# Ganggu.net
KiCad netlist of a schematic drawn in EAGLE
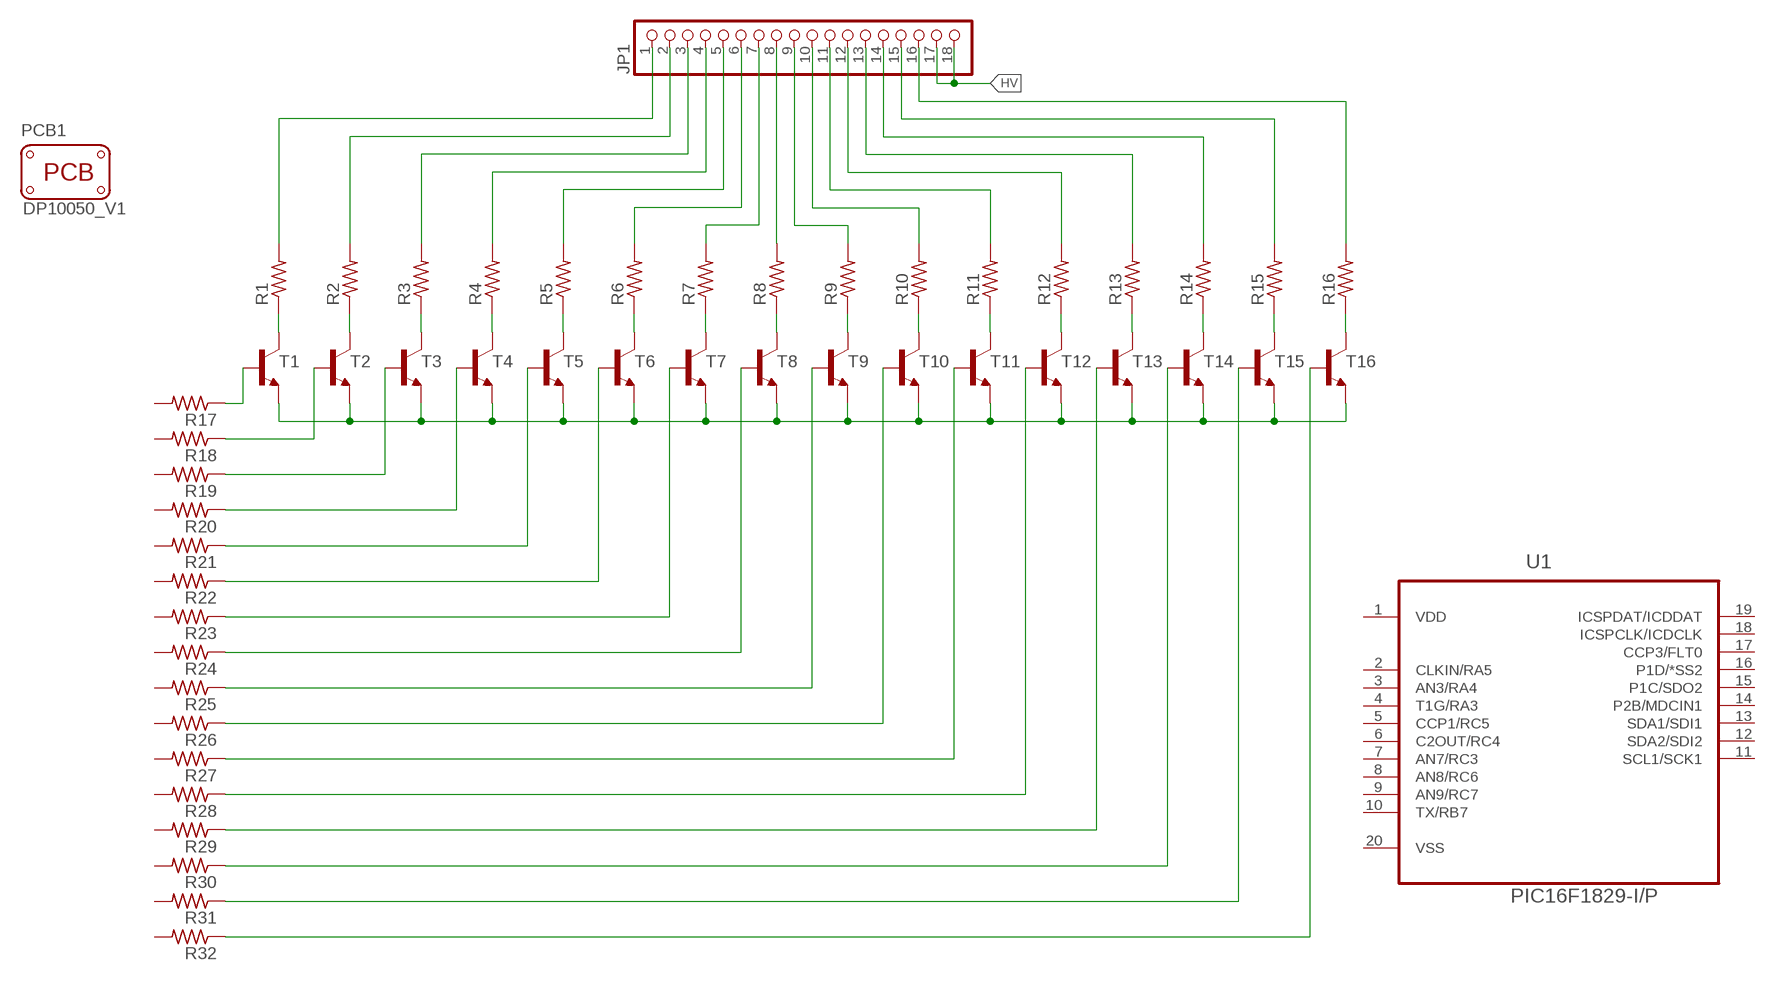
[diagram p0: schematic, sheet 1]

(export (version "E")
  (design (tool "Eeschema 10.0.6"))
  (components
    (comp (ref "JP1")
      (value "PINHD-1X18")
      (footprint "eagle-import:1X18")
      (libsource (lib "eagle-import") (part "PINHD-1X18"))
    )
    (comp (ref "PCB1")
      (value "PCB_DP_RECTANGLE-50X100")
      (footprint "eagle-import:DP10050_V1")
      (libsource (lib "eagle-import") (part "PCB_DP_RECTANGLE-50X100"))
    )
    (comp (ref "R1")
      (value "R-US_0207/9")
      (footprint "eagle-import:0207_9")
      (libsource (lib "eagle-import") (part "R-US_0207/9"))
    )
    (comp (ref "R2")
      (value "R-US_0207/9")
      (footprint "eagle-import:0207_9")
      (libsource (lib "eagle-import") (part "R-US_0207/9"))
    )
    (comp (ref "R3")
      (value "R-US_0207/9")
      (footprint "eagle-import:0207_9")
      (libsource (lib "eagle-import") (part "R-US_0207/9"))
    )
    (comp (ref "R4")
      (value "R-US_0207/9")
      (footprint "eagle-import:0207_9")
      (libsource (lib "eagle-import") (part "R-US_0207/9"))
    )
    (comp (ref "R5")
      (value "R-US_0207/9")
      (footprint "eagle-import:0207_9")
      (libsource (lib "eagle-import") (part "R-US_0207/9"))
    )
    (comp (ref "R6")
      (value "R-US_0207/9")
      (footprint "eagle-import:0207_9")
      (libsource (lib "eagle-import") (part "R-US_0207/9"))
    )
    (comp (ref "R7")
      (value "R-US_0207/9")
      (footprint "eagle-import:0207_9")
      (libsource (lib "eagle-import") (part "R-US_0207/9"))
    )
    (comp (ref "R8")
      (value "R-US_0207/9")
      (footprint "eagle-import:0207_9")
      (libsource (lib "eagle-import") (part "R-US_0207/9"))
    )
    (comp (ref "R9")
      (value "R-US_0207/9")
      (footprint "eagle-import:0207_9")
      (libsource (lib "eagle-import") (part "R-US_0207/9"))
    )
    (comp (ref "R10")
      (value "R-US_0207/9")
      (footprint "eagle-import:0207_9")
      (libsource (lib "eagle-import") (part "R-US_0207/9"))
    )
    (comp (ref "R11")
      (value "R-US_0207/9")
      (footprint "eagle-import:0207_9")
      (libsource (lib "eagle-import") (part "R-US_0207/9"))
    )
    (comp (ref "R12")
      (value "R-US_0207/9")
      (footprint "eagle-import:0207_9")
      (libsource (lib "eagle-import") (part "R-US_0207/9"))
    )
    (comp (ref "R13")
      (value "R-US_0207/9")
      (footprint "eagle-import:0207_9")
      (libsource (lib "eagle-import") (part "R-US_0207/9"))
    )
    (comp (ref "R14")
      (value "R-US_0207/9")
      (footprint "eagle-import:0207_9")
      (libsource (lib "eagle-import") (part "R-US_0207/9"))
    )
    (comp (ref "R15")
      (value "R-US_0207/9")
      (footprint "eagle-import:0207_9")
      (libsource (lib "eagle-import") (part "R-US_0207/9"))
    )
    (comp (ref "R16")
      (value "R-US_0207/9")
      (footprint "eagle-import:0207_9")
      (libsource (lib "eagle-import") (part "R-US_0207/9"))
    )
    (comp (ref "R17")
      (value "R-US_0207/9")
      (footprint "eagle-import:0207_9")
      (libsource (lib "eagle-import") (part "R-US_0207/9"))
    )
    (comp (ref "R18")
      (value "R-US_0207/9")
      (footprint "eagle-import:0207_9")
      (libsource (lib "eagle-import") (part "R-US_0207/9"))
    )
    (comp (ref "R19")
      (value "R-US_0207/9")
      (footprint "eagle-import:0207_9")
      (libsource (lib "eagle-import") (part "R-US_0207/9"))
    )
    (comp (ref "R20")
      (value "R-US_0207/9")
      (footprint "eagle-import:0207_9")
      (libsource (lib "eagle-import") (part "R-US_0207/9"))
    )
    (comp (ref "R21")
      (value "R-US_0207/9")
      (footprint "eagle-import:0207_9")
      (libsource (lib "eagle-import") (part "R-US_0207/9"))
    )
    (comp (ref "R22")
      (value "R-US_0207/9")
      (footprint "eagle-import:0207_9")
      (libsource (lib "eagle-import") (part "R-US_0207/9"))
    )
    (comp (ref "R23")
      (value "R-US_0207/9")
      (footprint "eagle-import:0207_9")
      (libsource (lib "eagle-import") (part "R-US_0207/9"))
    )
    (comp (ref "R24")
      (value "R-US_0207/9")
      (footprint "eagle-import:0207_9")
      (libsource (lib "eagle-import") (part "R-US_0207/9"))
    )
    (comp (ref "R25")
      (value "R-US_0207/9")
      (footprint "eagle-import:0207_9")
      (libsource (lib "eagle-import") (part "R-US_0207/9"))
    )
    (comp (ref "R26")
      (value "R-US_0207/9")
      (footprint "eagle-import:0207_9")
      (libsource (lib "eagle-import") (part "R-US_0207/9"))
    )
    (comp (ref "R27")
      (value "R-US_0207/9")
      (footprint "eagle-import:0207_9")
      (libsource (lib "eagle-import") (part "R-US_0207/9"))
    )
    (comp (ref "R28")
      (value "R-US_0207/9")
      (footprint "eagle-import:0207_9")
      (libsource (lib "eagle-import") (part "R-US_0207/9"))
    )
    (comp (ref "R29")
      (value "R-US_0207/9")
      (footprint "eagle-import:0207_9")
      (libsource (lib "eagle-import") (part "R-US_0207/9"))
    )
    (comp (ref "R30")
      (value "R-US_0207/9")
      (footprint "eagle-import:0207_9")
      (libsource (lib "eagle-import") (part "R-US_0207/9"))
    )
    (comp (ref "R31")
      (value "R-US_0207/9")
      (footprint "eagle-import:0207_9")
      (libsource (lib "eagle-import") (part "R-US_0207/9"))
    )
    (comp (ref "R32")
      (value "R-US_0207/9")
      (footprint "eagle-import:0207_9")
      (libsource (lib "eagle-import") (part "R-US_0207/9"))
    )
    (comp (ref "T1")
      (value "2N2222")
      (footprint "eagle-import:TO92-EBC-OVAL")
      (libsource (lib "eagle-import") (part "2N2222"))
    )
    (comp (ref "T2")
      (value "2N2222")
      (footprint "eagle-import:TO92-EBC-OVAL")
      (libsource (lib "eagle-import") (part "2N2222"))
    )
    (comp (ref "T3")
      (value "2N2222")
      (footprint "eagle-import:TO92-EBC-OVAL")
      (libsource (lib "eagle-import") (part "2N2222"))
    )
    (comp (ref "T4")
      (value "2N2222")
      (footprint "eagle-import:TO92-EBC-OVAL")
      (libsource (lib "eagle-import") (part "2N2222"))
    )
    (comp (ref "T5")
      (value "2N2222")
      (footprint "eagle-import:TO92-EBC-OVAL")
      (libsource (lib "eagle-import") (part "2N2222"))
    )
    (comp (ref "T6")
      (value "2N2222")
      (footprint "eagle-import:TO92-EBC-OVAL")
      (libsource (lib "eagle-import") (part "2N2222"))
    )
    (comp (ref "T7")
      (value "2N2222")
      (footprint "eagle-import:TO92-EBC-OVAL")
      (libsource (lib "eagle-import") (part "2N2222"))
    )
    (comp (ref "T8")
      (value "2N2222")
      (footprint "eagle-import:TO92-EBC-OVAL")
      (libsource (lib "eagle-import") (part "2N2222"))
    )
    (comp (ref "T9")
      (value "2N2222")
      (footprint "eagle-import:TO92-EBC-OVAL")
      (libsource (lib "eagle-import") (part "2N2222"))
    )
    (comp (ref "T10")
      (value "2N2222")
      (footprint "eagle-import:TO92-EBC-OVAL")
      (libsource (lib "eagle-import") (part "2N2222"))
    )
    (comp (ref "T11")
      (value "2N2222")
      (footprint "eagle-import:TO92-EBC-OVAL")
      (libsource (lib "eagle-import") (part "2N2222"))
    )
    (comp (ref "T12")
      (value "2N2222")
      (footprint "eagle-import:TO92-EBC-OVAL")
      (libsource (lib "eagle-import") (part "2N2222"))
    )
    (comp (ref "T13")
      (value "2N2222")
      (footprint "eagle-import:TO92-EBC-OVAL")
      (libsource (lib "eagle-import") (part "2N2222"))
    )
    (comp (ref "T14")
      (value "2N2222")
      (footprint "eagle-import:TO92-EBC-OVAL")
      (libsource (lib "eagle-import") (part "2N2222"))
    )
    (comp (ref "T15")
      (value "2N2222")
      (footprint "eagle-import:TO92-EBC-OVAL")
      (libsource (lib "eagle-import") (part "2N2222"))
    )
    (comp (ref "T16")
      (value "2N2222")
      (footprint "eagle-import:TO92-EBC-OVAL")
      (libsource (lib "eagle-import") (part "2N2222"))
    )
    (comp (ref "U1")
      (value "PIC16F1829-I/P")
      (footprint "eagle-import:DIP254P762X508-20P")
      (libsource (lib "eagle-import") (part "PIC16F1829-I/P"))
    )
  )
  (nets
    (net (code "1") (name "/VDD") (class "Default")
      (node (ref "U1") (pin "1") (pinfunction "VDD_1") (pintype "power_in"))
    )
    (net (code "2") (name "/VSS") (class "Default")
      (node (ref "U1") (pin "20") (pinfunction "VSS_20") (pintype "power_in"))
    )
    (net (code "3") (name "HV") (class "Default")
      (node (ref "JP1") (pin "17") (pinfunction "17_17") (pintype "passive"))
      (node (ref "JP1") (pin "18") (pinfunction "18_18") (pintype "passive"))
    )
    (net (code "4") (name "Net-(JP1-Pad1)") (class "Default")
      (node (ref "JP1") (pin "1") (pinfunction "1_1") (pintype "passive"))
      (node (ref "R1") (pin "2") (pinfunction "2_2") (pintype "passive"))
    )
    (net (code "5") (name "Net-(JP1-Pad2)") (class "Default")
      (node (ref "JP1") (pin "2") (pinfunction "2_2") (pintype "passive"))
      (node (ref "R2") (pin "2") (pinfunction "2_2") (pintype "passive"))
    )
    (net (code "6") (name "Net-(JP1-Pad3)") (class "Default")
      (node (ref "JP1") (pin "3") (pinfunction "3_3") (pintype "passive"))
      (node (ref "R3") (pin "2") (pinfunction "2_2") (pintype "passive"))
    )
    (net (code "7") (name "Net-(JP1-Pad4)") (class "Default")
      (node (ref "JP1") (pin "4") (pinfunction "4_4") (pintype "passive"))
      (node (ref "R4") (pin "2") (pinfunction "2_2") (pintype "passive"))
    )
    (net (code "8") (name "Net-(JP1-Pad5)") (class "Default")
      (node (ref "JP1") (pin "5") (pinfunction "5_5") (pintype "passive"))
      (node (ref "R5") (pin "2") (pinfunction "2_2") (pintype "passive"))
    )
    (net (code "9") (name "Net-(JP1-Pad6)") (class "Default")
      (node (ref "JP1") (pin "6") (pinfunction "6_6") (pintype "passive"))
      (node (ref "R6") (pin "2") (pinfunction "2_2") (pintype "passive"))
    )
    (net (code "10") (name "Net-(JP1-Pad7)") (class "Default")
      (node (ref "JP1") (pin "7") (pinfunction "7_7") (pintype "passive"))
      (node (ref "R7") (pin "2") (pinfunction "2_2") (pintype "passive"))
    )
    (net (code "11") (name "Net-(JP1-Pad8)") (class "Default")
      (node (ref "JP1") (pin "8") (pinfunction "8_8") (pintype "passive"))
      (node (ref "R8") (pin "2") (pinfunction "2_2") (pintype "passive"))
    )
    (net (code "12") (name "Net-(JP1-Pad9)") (class "Default")
      (node (ref "JP1") (pin "9") (pinfunction "9_9") (pintype "passive"))
      (node (ref "R9") (pin "2") (pinfunction "2_2") (pintype "passive"))
    )
    (net (code "13") (name "Net-(JP1-Pad10)") (class "Default")
      (node (ref "JP1") (pin "10") (pinfunction "10_10") (pintype "passive"))
      (node (ref "R10") (pin "2") (pinfunction "2_2") (pintype "passive"))
    )
    (net (code "14") (name "Net-(JP1-Pad11)") (class "Default")
      (node (ref "JP1") (pin "11") (pinfunction "11_11") (pintype "passive"))
      (node (ref "R11") (pin "2") (pinfunction "2_2") (pintype "passive"))
    )
    (net (code "15") (name "Net-(JP1-Pad12)") (class "Default")
      (node (ref "JP1") (pin "12") (pinfunction "12_12") (pintype "passive"))
      (node (ref "R12") (pin "2") (pinfunction "2_2") (pintype "passive"))
    )
    (net (code "16") (name "Net-(JP1-Pad13)") (class "Default")
      (node (ref "JP1") (pin "13") (pinfunction "13_13") (pintype "passive"))
      (node (ref "R13") (pin "2") (pinfunction "2_2") (pintype "passive"))
    )
    (net (code "17") (name "Net-(JP1-Pad14)") (class "Default")
      (node (ref "JP1") (pin "14") (pinfunction "14_14") (pintype "passive"))
      (node (ref "R14") (pin "2") (pinfunction "2_2") (pintype "passive"))
    )
    (net (code "18") (name "Net-(JP1-Pad15)") (class "Default")
      (node (ref "JP1") (pin "15") (pinfunction "15_15") (pintype "passive"))
      (node (ref "R15") (pin "2") (pinfunction "2_2") (pintype "passive"))
    )
    (net (code "19") (name "Net-(JP1-Pad16)") (class "Default")
      (node (ref "JP1") (pin "16") (pinfunction "16_16") (pintype "passive"))
      (node (ref "R16") (pin "2") (pinfunction "2_2") (pintype "passive"))
    )
    (net (code "20") (name "Net-(R1-Pad1)") (class "Default")
      (node (ref "R1") (pin "1") (pinfunction "1_1") (pintype "passive"))
      (node (ref "T1") (pin "C") (pinfunction "C_C") (pintype "passive"))
    )
    (net (code "21") (name "Net-(R2-Pad1)") (class "Default")
      (node (ref "R2") (pin "1") (pinfunction "1_1") (pintype "passive"))
      (node (ref "T2") (pin "C") (pinfunction "C_C") (pintype "passive"))
    )
    (net (code "22") (name "Net-(R3-Pad1)") (class "Default")
      (node (ref "R3") (pin "1") (pinfunction "1_1") (pintype "passive"))
      (node (ref "T3") (pin "C") (pinfunction "C_C") (pintype "passive"))
    )
    (net (code "23") (name "Net-(R4-Pad1)") (class "Default")
      (node (ref "R4") (pin "1") (pinfunction "1_1") (pintype "passive"))
      (node (ref "T4") (pin "C") (pinfunction "C_C") (pintype "passive"))
    )
    (net (code "24") (name "Net-(R5-Pad1)") (class "Default")
      (node (ref "R5") (pin "1") (pinfunction "1_1") (pintype "passive"))
      (node (ref "T5") (pin "C") (pinfunction "C_C") (pintype "passive"))
    )
    (net (code "25") (name "Net-(R6-Pad1)") (class "Default")
      (node (ref "R6") (pin "1") (pinfunction "1_1") (pintype "passive"))
      (node (ref "T6") (pin "C") (pinfunction "C_C") (pintype "passive"))
    )
    (net (code "26") (name "Net-(R7-Pad1)") (class "Default")
      (node (ref "R7") (pin "1") (pinfunction "1_1") (pintype "passive"))
      (node (ref "T7") (pin "C") (pinfunction "C_C") (pintype "passive"))
    )
    (net (code "27") (name "Net-(R8-Pad1)") (class "Default")
      (node (ref "R8") (pin "1") (pinfunction "1_1") (pintype "passive"))
      (node (ref "T8") (pin "C") (pinfunction "C_C") (pintype "passive"))
    )
    (net (code "28") (name "Net-(R9-Pad1)") (class "Default")
      (node (ref "R9") (pin "1") (pinfunction "1_1") (pintype "passive"))
      (node (ref "T9") (pin "C") (pinfunction "C_C") (pintype "passive"))
    )
    (net (code "29") (name "Net-(R10-Pad1)") (class "Default")
      (node (ref "R10") (pin "1") (pinfunction "1_1") (pintype "passive"))
      (node (ref "T10") (pin "C") (pinfunction "C_C") (pintype "passive"))
    )
    (net (code "30") (name "Net-(R11-Pad1)") (class "Default")
      (node (ref "R11") (pin "1") (pinfunction "1_1") (pintype "passive"))
      (node (ref "T11") (pin "C") (pinfunction "C_C") (pintype "passive"))
    )
    (net (code "31") (name "Net-(R12-Pad1)") (class "Default")
      (node (ref "R12") (pin "1") (pinfunction "1_1") (pintype "passive"))
      (node (ref "T12") (pin "C") (pinfunction "C_C") (pintype "passive"))
    )
    (net (code "32") (name "Net-(R13-Pad1)") (class "Default")
      (node (ref "R13") (pin "1") (pinfunction "1_1") (pintype "passive"))
      (node (ref "T13") (pin "C") (pinfunction "C_C") (pintype "passive"))
    )
    (net (code "33") (name "Net-(R14-Pad1)") (class "Default")
      (node (ref "R14") (pin "1") (pinfunction "1_1") (pintype "passive"))
      (node (ref "T14") (pin "C") (pinfunction "C_C") (pintype "passive"))
    )
    (net (code "34") (name "Net-(R15-Pad1)") (class "Default")
      (node (ref "R15") (pin "1") (pinfunction "1_1") (pintype "passive"))
      (node (ref "T15") (pin "C") (pinfunction "C_C") (pintype "passive"))
    )
    (net (code "35") (name "Net-(R16-Pad1)") (class "Default")
      (node (ref "R16") (pin "1") (pinfunction "1_1") (pintype "passive"))
      (node (ref "T16") (pin "C") (pinfunction "C_C") (pintype "passive"))
    )
    (net (code "36") (name "Net-(R17-Pad1)") (class "Default")
      (node (ref "R17") (pin "1") (pinfunction "1_1") (pintype "passive"))
      (node (ref "T1") (pin "B") (pinfunction "B_B") (pintype "passive"))
    )
    (net (code "37") (name "Net-(R18-Pad1)") (class "Default")
      (node (ref "R18") (pin "1") (pinfunction "1_1") (pintype "passive"))
      (node (ref "T2") (pin "B") (pinfunction "B_B") (pintype "passive"))
    )
    (net (code "38") (name "Net-(R19-Pad1)") (class "Default")
      (node (ref "R19") (pin "1") (pinfunction "1_1") (pintype "passive"))
      (node (ref "T3") (pin "B") (pinfunction "B_B") (pintype "passive"))
    )
    (net (code "39") (name "Net-(R20-Pad1)") (class "Default")
      (node (ref "R20") (pin "1") (pinfunction "1_1") (pintype "passive"))
      (node (ref "T4") (pin "B") (pinfunction "B_B") (pintype "passive"))
    )
    (net (code "40") (name "Net-(R21-Pad1)") (class "Default")
      (node (ref "R21") (pin "1") (pinfunction "1_1") (pintype "passive"))
      (node (ref "T5") (pin "B") (pinfunction "B_B") (pintype "passive"))
    )
    (net (code "41") (name "Net-(R22-Pad1)") (class "Default")
      (node (ref "R22") (pin "1") (pinfunction "1_1") (pintype "passive"))
      (node (ref "T6") (pin "B") (pinfunction "B_B") (pintype "passive"))
    )
    (net (code "42") (name "Net-(R23-Pad1)") (class "Default")
      (node (ref "R23") (pin "1") (pinfunction "1_1") (pintype "passive"))
      (node (ref "T7") (pin "B") (pinfunction "B_B") (pintype "passive"))
    )
    (net (code "43") (name "Net-(R24-Pad1)") (class "Default")
      (node (ref "R24") (pin "1") (pinfunction "1_1") (pintype "passive"))
      (node (ref "T8") (pin "B") (pinfunction "B_B") (pintype "passive"))
    )
    (net (code "44") (name "Net-(R25-Pad1)") (class "Default")
      (node (ref "R25") (pin "1") (pinfunction "1_1") (pintype "passive"))
      (node (ref "T9") (pin "B") (pinfunction "B_B") (pintype "passive"))
    )
    (net (code "45") (name "Net-(R26-Pad1)") (class "Default")
      (node (ref "R26") (pin "1") (pinfunction "1_1") (pintype "passive"))
      (node (ref "T10") (pin "B") (pinfunction "B_B") (pintype "passive"))
    )
    (net (code "46") (name "Net-(R27-Pad1)") (class "Default")
      (node (ref "R27") (pin "1") (pinfunction "1_1") (pintype "passive"))
      (node (ref "T11") (pin "B") (pinfunction "B_B") (pintype "passive"))
    )
    (net (code "47") (name "Net-(R28-Pad1)") (class "Default")
      (node (ref "R28") (pin "1") (pinfunction "1_1") (pintype "passive"))
      (node (ref "T12") (pin "B") (pinfunction "B_B") (pintype "passive"))
    )
    (net (code "48") (name "Net-(R29-Pad1)") (class "Default")
      (node (ref "R29") (pin "1") (pinfunction "1_1") (pintype "passive"))
      (node (ref "T13") (pin "B") (pinfunction "B_B") (pintype "passive"))
    )
    (net (code "49") (name "Net-(R30-Pad1)") (class "Default")
      (node (ref "R30") (pin "1") (pinfunction "1_1") (pintype "passive"))
      (node (ref "T14") (pin "B") (pinfunction "B_B") (pintype "passive"))
    )
    (net (code "50") (name "Net-(R31-Pad1)") (class "Default")
      (node (ref "R31") (pin "1") (pinfunction "1_1") (pintype "passive"))
      (node (ref "T15") (pin "B") (pinfunction "B_B") (pintype "passive"))
    )
    (net (code "51") (name "Net-(R32-Pad1)") (class "Default")
      (node (ref "R32") (pin "1") (pinfunction "1_1") (pintype "passive"))
      (node (ref "T16") (pin "B") (pinfunction "B_B") (pintype "passive"))
    )
    (net (code "52") (name "Net-(T1-PadE)") (class "Default")
      (node (ref "T1") (pin "E") (pinfunction "E_E") (pintype "passive"))
      (node (ref "T10") (pin "E") (pinfunction "E_E") (pintype "passive"))
      (node (ref "T11") (pin "E") (pinfunction "E_E") (pintype "passive"))
      (node (ref "T12") (pin "E") (pinfunction "E_E") (pintype "passive"))
      (node (ref "T13") (pin "E") (pinfunction "E_E") (pintype "passive"))
      (node (ref "T14") (pin "E") (pinfunction "E_E") (pintype "passive"))
      (node (ref "T15") (pin "E") (pinfunction "E_E") (pintype "passive"))
      (node (ref "T16") (pin "E") (pinfunction "E_E") (pintype "passive"))
      (node (ref "T2") (pin "E") (pinfunction "E_E") (pintype "passive"))
      (node (ref "T3") (pin "E") (pinfunction "E_E") (pintype "passive"))
      (node (ref "T4") (pin "E") (pinfunction "E_E") (pintype "passive"))
      (node (ref "T5") (pin "E") (pinfunction "E_E") (pintype "passive"))
      (node (ref "T6") (pin "E") (pinfunction "E_E") (pintype "passive"))
      (node (ref "T7") (pin "E") (pinfunction "E_E") (pintype "passive"))
      (node (ref "T8") (pin "E") (pinfunction "E_E") (pintype "passive"))
      (node (ref "T9") (pin "E") (pinfunction "E_E") (pintype "passive"))
    )
    (net (code "53") (name "unconnected-(R17-Pad2)") (class "Default")
      (node (ref "R17") (pin "2") (pinfunction "2_2") (pintype "passive"))
    )
    (net (code "54") (name "unconnected-(R18-Pad2)") (class "Default")
      (node (ref "R18") (pin "2") (pinfunction "2_2") (pintype "passive"))
    )
    (net (code "55") (name "unconnected-(R19-Pad2)") (class "Default")
      (node (ref "R19") (pin "2") (pinfunction "2_2") (pintype "passive"))
    )
    (net (code "56") (name "unconnected-(R20-Pad2)") (class "Default")
      (node (ref "R20") (pin "2") (pinfunction "2_2") (pintype "passive"))
    )
    (net (code "57") (name "unconnected-(R21-Pad2)") (class "Default")
      (node (ref "R21") (pin "2") (pinfunction "2_2") (pintype "passive"))
    )
    (net (code "58") (name "unconnected-(R22-Pad2)") (class "Default")
      (node (ref "R22") (pin "2") (pinfunction "2_2") (pintype "passive"))
    )
    (net (code "59") (name "unconnected-(R23-Pad2)") (class "Default")
      (node (ref "R23") (pin "2") (pinfunction "2_2") (pintype "passive"))
    )
    (net (code "60") (name "unconnected-(R24-Pad2)") (class "Default")
      (node (ref "R24") (pin "2") (pinfunction "2_2") (pintype "passive"))
    )
    (net (code "61") (name "unconnected-(R25-Pad2)") (class "Default")
      (node (ref "R25") (pin "2") (pinfunction "2_2") (pintype "passive"))
    )
    (net (code "62") (name "unconnected-(R26-Pad2)") (class "Default")
      (node (ref "R26") (pin "2") (pinfunction "2_2") (pintype "passive"))
    )
    (net (code "63") (name "unconnected-(R27-Pad2)") (class "Default")
      (node (ref "R27") (pin "2") (pinfunction "2_2") (pintype "passive"))
    )
    (net (code "64") (name "unconnected-(R28-Pad2)") (class "Default")
      (node (ref "R28") (pin "2") (pinfunction "2_2") (pintype "passive"))
    )
    (net (code "65") (name "unconnected-(R29-Pad2)") (class "Default")
      (node (ref "R29") (pin "2") (pinfunction "2_2") (pintype "passive"))
    )
    (net (code "66") (name "unconnected-(R30-Pad2)") (class "Default")
      (node (ref "R30") (pin "2") (pinfunction "2_2") (pintype "passive"))
    )
    (net (code "67") (name "unconnected-(R31-Pad2)") (class "Default")
      (node (ref "R31") (pin "2") (pinfunction "2_2") (pintype "passive"))
    )
    (net (code "68") (name "unconnected-(R32-Pad2)") (class "Default")
      (node (ref "R32") (pin "2") (pinfunction "2_2") (pintype "passive"))
    )
    (net (code "69") (name "unconnected-(U1-AN3{slash}RA4-Pad3)") (class "Default")
      (node (ref "U1") (pin "3") (pinfunction "AN3/RA4_3") (pintype "bidirectional"))
    )
    (net (code "70") (name "unconnected-(U1-AN7{slash}RC3-Pad7)") (class "Default")
      (node (ref "U1") (pin "7") (pinfunction "AN7/RC3_7") (pintype "bidirectional"))
    )
    (net (code "71") (name "unconnected-(U1-AN8{slash}RC6-Pad8)") (class "Default")
      (node (ref "U1") (pin "8") (pinfunction "AN8/RC6_8") (pintype "bidirectional"))
    )
    (net (code "72") (name "unconnected-(U1-AN9{slash}RC7-Pad9)") (class "Default")
      (node (ref "U1") (pin "9") (pinfunction "AN9/RC7_9") (pintype "bidirectional"))
    )
    (net (code "73") (name "unconnected-(U1-C2OUT{slash}RC4-Pad6)") (class "Default")
      (node (ref "U1") (pin "6") (pinfunction "C2OUT/RC4_6") (pintype "bidirectional"))
    )
    (net (code "74") (name "unconnected-(U1-CCP1{slash}RC5-Pad5)") (class "Default")
      (node (ref "U1") (pin "5") (pinfunction "CCP1/RC5_5") (pintype "bidirectional"))
    )
    (net (code "75") (name "unconnected-(U1-CCP3{slash}FLT0-Pad17)") (class "Default")
      (node (ref "U1") (pin "17") (pinfunction "CCP3/FLT0_17") (pintype "bidirectional"))
    )
    (net (code "76") (name "unconnected-(U1-CLKIN{slash}RA5-Pad2)") (class "Default")
      (node (ref "U1") (pin "2") (pinfunction "CLKIN/RA5_2") (pintype "bidirectional"))
    )
    (net (code "77") (name "unconnected-(U1-ICSPCLK{slash}ICDCLK-Pad18)") (class "Default")
      (node (ref "U1") (pin "18") (pinfunction "ICSPCLK/ICDCLK_18") (pintype "bidirectional"))
    )
    (net (code "78") (name "unconnected-(U1-ICSPDAT{slash}ICDDAT-Pad19)") (class "Default")
      (node (ref "U1") (pin "19") (pinfunction "ICSPDAT/ICDDAT_19") (pintype "bidirectional"))
    )
    (net (code "79") (name "unconnected-(U1-P1C{slash}SDO2-Pad15)") (class "Default")
      (node (ref "U1") (pin "15") (pinfunction "P1C/SDO2_15") (pintype "bidirectional"))
    )
    (net (code "80") (name "unconnected-(U1-P1D{slash}*SS2-Pad16)") (class "Default")
      (node (ref "U1") (pin "16") (pinfunction "P1D/*SS2_16") (pintype "bidirectional"))
    )
    (net (code "81") (name "unconnected-(U1-P2B{slash}MDCIN1-Pad14)") (class "Default")
      (node (ref "U1") (pin "14") (pinfunction "P2B/MDCIN1_14") (pintype "bidirectional"))
    )
    (net (code "82") (name "unconnected-(U1-SCL1{slash}SCK1-Pad11)") (class "Default")
      (node (ref "U1") (pin "11") (pinfunction "SCL1/SCK1_11") (pintype "bidirectional"))
    )
    (net (code "83") (name "unconnected-(U1-SDA1{slash}SDI1-Pad13)") (class "Default")
      (node (ref "U1") (pin "13") (pinfunction "SDA1/SDI1_13") (pintype "bidirectional"))
    )
    (net (code "84") (name "unconnected-(U1-SDA2{slash}SDI2-Pad12)") (class "Default")
      (node (ref "U1") (pin "12") (pinfunction "SDA2/SDI2_12") (pintype "bidirectional"))
    )
    (net (code "85") (name "unconnected-(U1-T1G{slash}RA3-Pad4)") (class "Default")
      (node (ref "U1") (pin "4") (pinfunction "T1G/RA3_4") (pintype "bidirectional"))
    )
    (net (code "86") (name "unconnected-(U1-TX{slash}RB7-Pad10)") (class "Default")
      (node (ref "U1") (pin "10") (pinfunction "TX/RB7_10") (pintype "bidirectional"))
    )
  )
)
